# DD2090_4CAM_FFC_TopLevel.net
KiCad netlist of a schematic drawn in Altium Designer
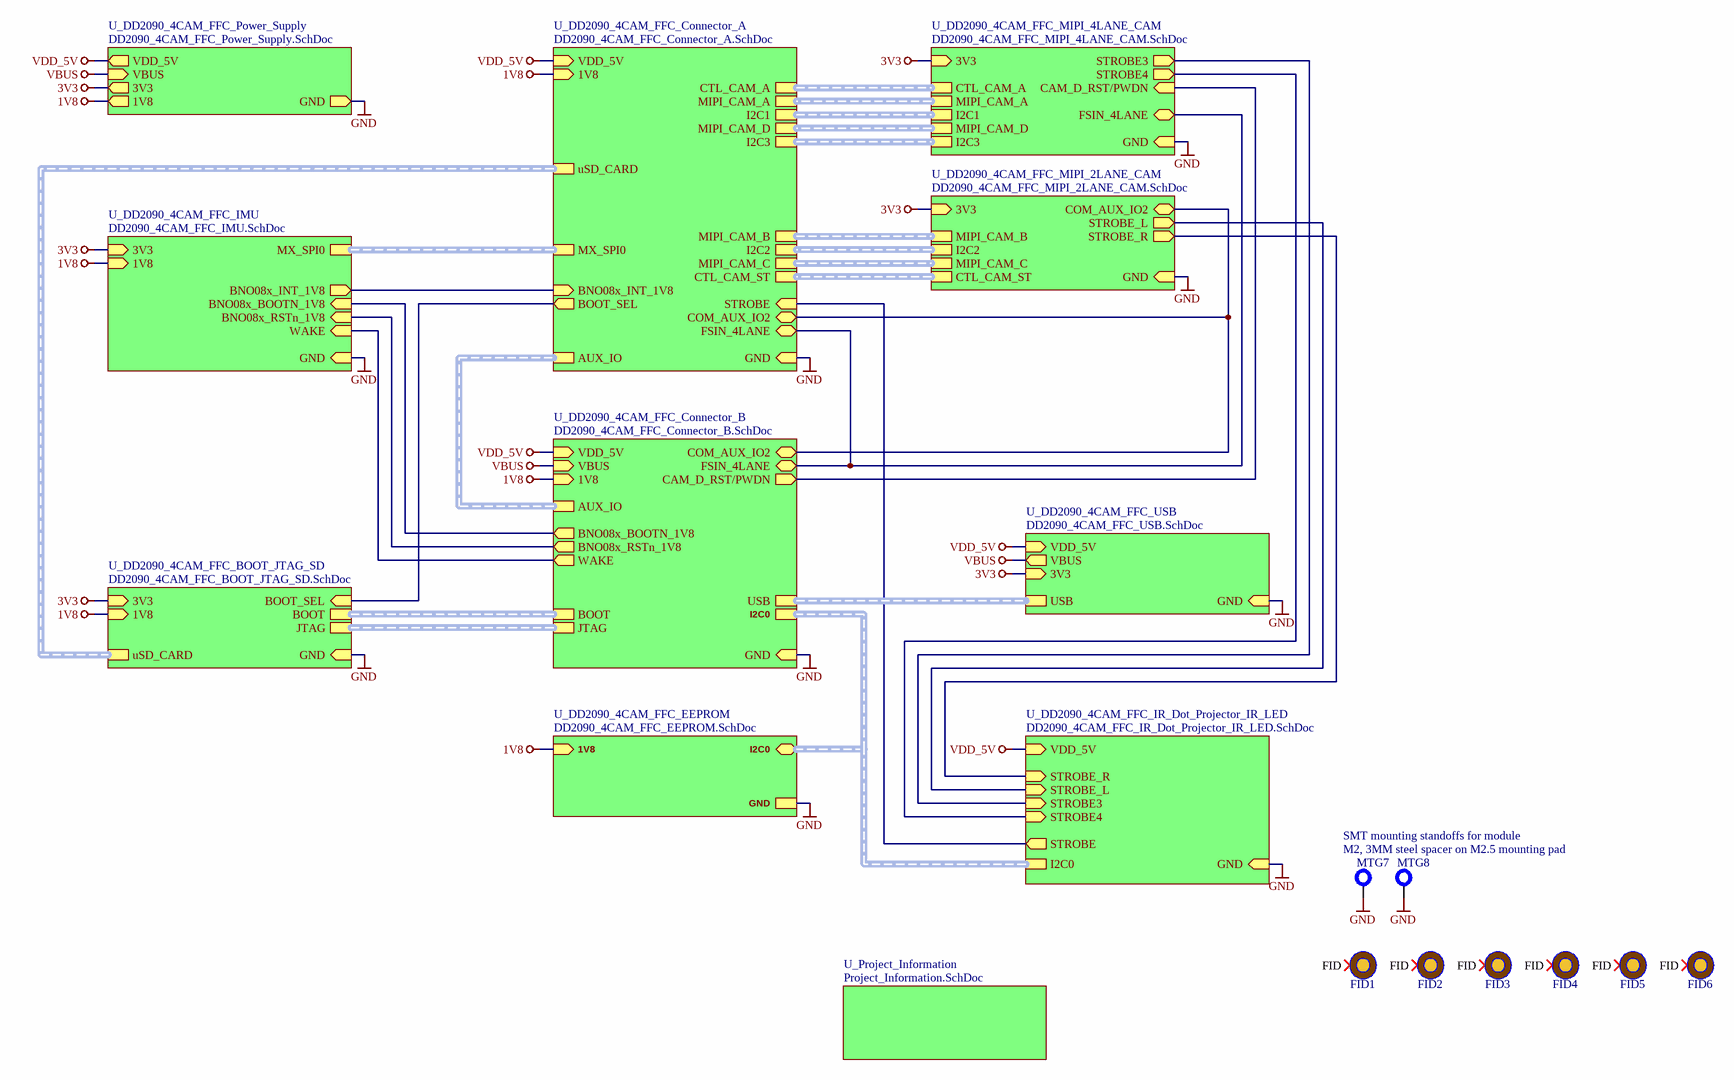
[diagram p0: DD2090_4CAM_FFC_TopLevel.SchDoc]

(export (version "E")
  (design (tool "Eeschema 10.0.6"))
  (components
    (comp (ref "FID1")
      (value "FIDUCIAL_ROUND_1MM")
      (footprint "LuxonisMaster:FIDUCIAL_ROUND_1MM")
      (description "Fiducial with various available footprints")
      (libsource (lib "LuxonisMaster") (part "FIDUCIAL"))
    )
    (comp (ref "FID2")
      (value "FIDUCIAL_ROUND_1MM")
      (footprint "LuxonisMaster:FIDUCIAL_ROUND_1MM")
      (description "Fiducial with various available footprints")
      (libsource (lib "LuxonisMaster") (part "FIDUCIAL"))
    )
    (comp (ref "FID3")
      (value "FIDUCIAL_ROUND_1MM")
      (footprint "LuxonisMaster:FIDUCIAL_ROUND_1MM")
      (description "Fiducial with various available footprints")
      (libsource (lib "LuxonisMaster") (part "FIDUCIAL"))
    )
    (comp (ref "FID4")
      (value "FIDUCIAL_ROUND_1MM")
      (footprint "LuxonisMaster:FIDUCIAL_ROUND_1MM")
      (description "Fiducial with various available footprints")
      (libsource (lib "LuxonisMaster") (part "FIDUCIAL"))
    )
    (comp (ref "FID5")
      (value "FIDUCIAL_ROUND_1MM")
      (footprint "LuxonisMaster:FIDUCIAL_ROUND_1MM")
      (description "Fiducial with various available footprints")
      (libsource (lib "LuxonisMaster") (part "FIDUCIAL"))
    )
    (comp (ref "FID6")
      (value "FIDUCIAL_ROUND_1MM")
      (footprint "LuxonisMaster:FIDUCIAL_ROUND_1MM")
      (description "Fiducial with various available footprints")
      (libsource (lib "LuxonisMaster") (part "FIDUCIAL"))
    )
    (comp (ref "MTG7")
      (value "M2, 3MM steel spacer on M2.5 mounting pad")
      (footprint "LuxonisMaster:9774030243R")
      (description "MP ROUND STANDOFF M2X0.4 STEEL 3MM")
      (libsource (lib "LuxonisMaster") (part "9774030243R"))
    )
    (comp (ref "MTG8")
      (value "M2, 3MM steel spacer on M2.5 mounting pad")
      (footprint "LuxonisMaster:9774030243R")
      (description "MP ROUND STANDOFF M2X0.4 STEEL 3MM")
      (libsource (lib "LuxonisMaster") (part "9774030243R"))
    )
  )
  (nets
    (net (code "32") (name "GND") (class "Default")
      (node (ref "MTG7") (pin "1") (pintype "passive"))
      (node (ref "MTG8") (pin "1") (pintype "passive"))
    )
    (net (code "35") (name "unconnected-(FID1-PadFID)") (class "Default")
      (node (ref "FID1") (pin "FID") (pinfunction "FID_FID") (pintype "input+no_connect"))
    )
    (net (code "36") (name "unconnected-(FID2-PadFID)") (class "Default")
      (node (ref "FID2") (pin "FID") (pinfunction "FID_FID") (pintype "input+no_connect"))
    )
    (net (code "37") (name "unconnected-(FID3-PadFID)") (class "Default")
      (node (ref "FID3") (pin "FID") (pinfunction "FID_FID") (pintype "input+no_connect"))
    )
    (net (code "38") (name "unconnected-(FID4-PadFID)") (class "Default")
      (node (ref "FID4") (pin "FID") (pinfunction "FID_FID") (pintype "input+no_connect"))
    )
    (net (code "39") (name "unconnected-(FID5-PadFID)") (class "Default")
      (node (ref "FID5") (pin "FID") (pinfunction "FID_FID") (pintype "input+no_connect"))
    )
    (net (code "40") (name "unconnected-(FID6-PadFID)") (class "Default")
      (node (ref "FID6") (pin "FID") (pinfunction "FID_FID") (pintype "input+no_connect"))
    )
  )
)
